# Payload.net
KiCad netlist of a schematic drawn in Altium Designer
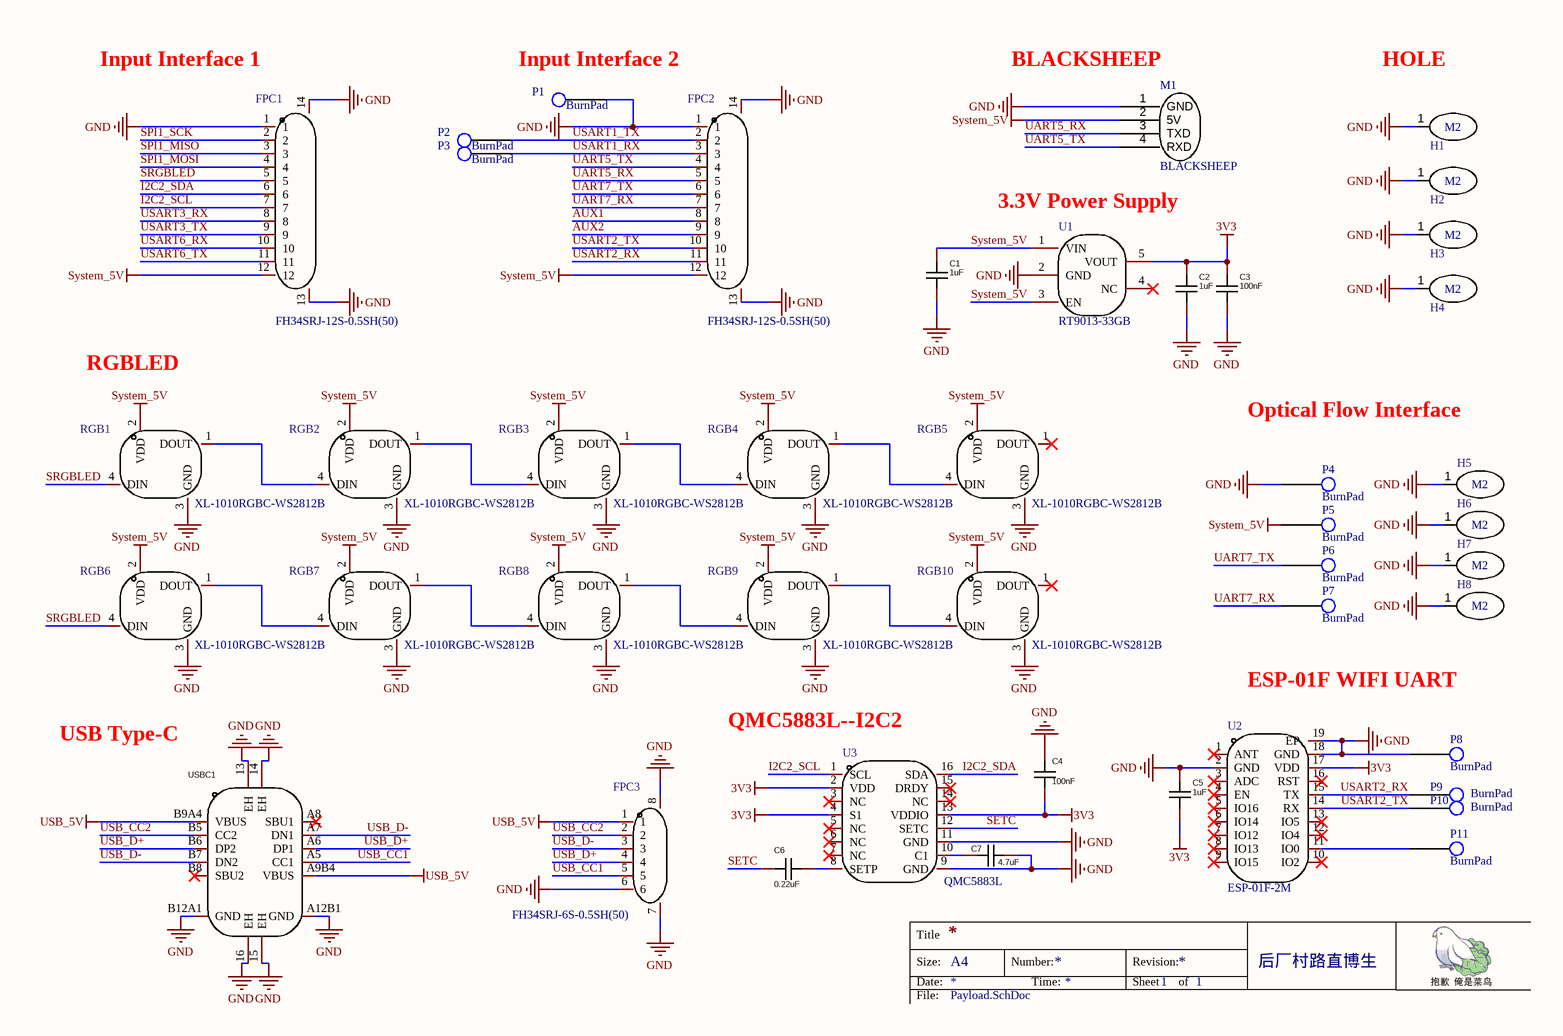
[diagram p0: Payload.SchDoc]

(export (version "E")
  (design (tool "Eeschema 10.0.6"))
  (components
    (comp (ref "C1")
      (value "1uF")
      (footprint "C0402")
      (libsource (lib "Capacitor") (part "CC0603KRX7R9BB104"))
    )
    (comp (ref "C2")
      (value "1uF")
      (footprint "C0402")
      (libsource (lib "Capacitor") (part "CC0603KRX7R9BB104"))
    )
    (comp (ref "C3")
      (value "100nF")
      (footprint "C0201")
      (libsource (lib "Capacitor") (part "CC0603KRX7R9BB104"))
    )
    (comp (ref "C4")
      (value "100nF")
      (footprint "C0201")
      (libsource (lib "Capacitor") (part "CC0603KRX7R9BB104"))
    )
    (comp (ref "C5")
      (value "1uF")
      (footprint "C0402")
      (libsource (lib "Capacitor") (part "CC0603KRX7R9BB104"))
    )
    (comp (ref "C6")
      (value "0.22uF")
      (footprint "C0402")
      (libsource (lib "Capacitor") (part "CC0603KRX7R9BB104"))
    )
    (comp (ref "C7")
      (value "4.7uF")
      (footprint "C0402")
      (libsource (lib "Capacitor") (part "CC0603KRX7R9BB104"))
    )
    (comp (ref "FPC1")
      (value "FH34SRJ-12S-0.5SH(50)")
      (footprint "FFC-SMD_12P-P0.50_FH34SRJ-12S-0.5SH")
      (fields (field (name "MANUFACTURER") "HRS(广濑)"))
      (libsource (lib "FPC") (part "FH34SRJ-12S-0.5SH(50)"))
    )
    (comp (ref "FPC2")
      (value "FH34SRJ-12S-0.5SH(50)")
      (footprint "FFC-SMD_12P-P0.50_FH34SRJ-12S-0.5SH")
      (fields (field (name "MANUFACTURER") "HRS(广濑)"))
      (libsource (lib "FPC") (part "FH34SRJ-12S-0.5SH(50)"))
    )
    (comp (ref "FPC3")
      (value "FH34SRJ-6S-0.5SH(50)")
      (footprint "FFC-SMD_6P-P0.50_FH34SRJ-6S-0.5SH")
      (fields (field (name "MANUFACTURER") "HRS(广濑)"))
      (libsource (lib "FPC") (part "FH34SRJ-6S-0.5SH(50)"))
    )
    (comp (ref "H1") (value "M2_HOLE") (footprint "M2_HOLE") (libsource (lib "HOLE") (part "M2_HOLE")))
    (comp (ref "H2") (value "M2_HOLE") (footprint "M2_HOLE") (libsource (lib "HOLE") (part "M2_HOLE")))
    (comp (ref "H3") (value "M2_HOLE") (footprint "M2_HOLE") (libsource (lib "HOLE") (part "M2_HOLE")))
    (comp (ref "H4") (value "M2_HOLE") (footprint "M2_HOLE") (libsource (lib "HOLE") (part "M2_HOLE")))
    (comp (ref "H5") (value "M2_HOLE") (footprint "M2_HOLE") (libsource (lib "HOLE") (part "M2_HOLE")))
    (comp (ref "H6") (value "M2_HOLE") (footprint "M2_HOLE") (libsource (lib "HOLE") (part "M2_HOLE")))
    (comp (ref "H7") (value "M2_HOLE") (footprint "M2_HOLE") (libsource (lib "HOLE") (part "M2_HOLE")))
    (comp (ref "H8") (value "M2_HOLE") (footprint "M2_HOLE") (libsource (lib "HOLE") (part "M2_HOLE")))
    (comp (ref "M1")
      (value "BLACKSHEEP")
      (footprint "BLACKSHEEP")
      (libsource (lib "Module") (part "BLACKSHEEP"))
    )
    (comp (ref "P1") (value "BurnPad") (footprint "BurnPad_0.8mm") (libsource (lib "Pad") (part "BurnPad")))
    (comp (ref "P2") (value "BurnPad") (footprint "BurnPad_0.8mm") (libsource (lib "Pad") (part "BurnPad")))
    (comp (ref "P3") (value "BurnPad") (footprint "BurnPad_0.8mm") (libsource (lib "Pad") (part "BurnPad")))
    (comp (ref "P4") (value "BurnPad") (footprint "BurnPad_0.8mm") (libsource (lib "Pad") (part "BurnPad")))
    (comp (ref "P5") (value "BurnPad") (footprint "BurnPad_0.8mm") (libsource (lib "Pad") (part "BurnPad")))
    (comp (ref "P6") (value "BurnPad") (footprint "BurnPad_0.8mm") (libsource (lib "Pad") (part "BurnPad")))
    (comp (ref "P7") (value "BurnPad") (footprint "BurnPad_0.8mm") (libsource (lib "Pad") (part "BurnPad")))
    (comp (ref "P8") (value "BurnPad") (footprint "BurnPad_0.8mm") (libsource (lib "Pad") (part "BurnPad")))
    (comp (ref "P9") (value "BurnPad") (footprint "BurnPad_0.8mm") (libsource (lib "Pad") (part "BurnPad")))
    (comp (ref "P10") (value "BurnPad") (footprint "BurnPad_0.8mm") (libsource (lib "Pad") (part "BurnPad")))
    (comp (ref "P11") (value "BurnPad") (footprint "BurnPad_0.8mm") (libsource (lib "Pad") (part "BurnPad")))
    (comp (ref "RGB1")
      (value "XL-1010RGBC-WS2812B")
      (footprint "LED-SMD_4P-L1.0-W1.0-TL_XL-1010RGBC-WS2812B")
      (fields (field (name "MANUFACTURER") "XINGLIGHT(成兴光)"))
      (libsource (lib "RGB") (part "XL-1010RGBC-WS2812B"))
    )
    (comp (ref "RGB2")
      (value "XL-1010RGBC-WS2812B")
      (footprint "LED-SMD_4P-L1.0-W1.0-TL_XL-1010RGBC-WS2812B")
      (fields (field (name "MANUFACTURER") "XINGLIGHT(成兴光)"))
      (libsource (lib "RGB") (part "XL-1010RGBC-WS2812B"))
    )
    (comp (ref "RGB3")
      (value "XL-1010RGBC-WS2812B")
      (footprint "LED-SMD_4P-L1.0-W1.0-TL_XL-1010RGBC-WS2812B")
      (fields (field (name "MANUFACTURER") "XINGLIGHT(成兴光)"))
      (libsource (lib "RGB") (part "XL-1010RGBC-WS2812B"))
    )
    (comp (ref "RGB4")
      (value "XL-1010RGBC-WS2812B")
      (footprint "LED-SMD_4P-L1.0-W1.0-TL_XL-1010RGBC-WS2812B")
      (fields (field (name "MANUFACTURER") "XINGLIGHT(成兴光)"))
      (libsource (lib "RGB") (part "XL-1010RGBC-WS2812B"))
    )
    (comp (ref "RGB5")
      (value "XL-1010RGBC-WS2812B")
      (footprint "LED-SMD_4P-L1.0-W1.0-TL_XL-1010RGBC-WS2812B")
      (fields (field (name "MANUFACTURER") "XINGLIGHT(成兴光)"))
      (libsource (lib "RGB") (part "XL-1010RGBC-WS2812B"))
    )
    (comp (ref "RGB6")
      (value "XL-1010RGBC-WS2812B")
      (footprint "LED-SMD_4P-L1.0-W1.0-TL_XL-1010RGBC-WS2812B")
      (fields (field (name "MANUFACTURER") "XINGLIGHT(成兴光)"))
      (libsource (lib "RGB") (part "XL-1010RGBC-WS2812B"))
    )
    (comp (ref "RGB7")
      (value "XL-1010RGBC-WS2812B")
      (footprint "LED-SMD_4P-L1.0-W1.0-TL_XL-1010RGBC-WS2812B")
      (fields (field (name "MANUFACTURER") "XINGLIGHT(成兴光)"))
      (libsource (lib "RGB") (part "XL-1010RGBC-WS2812B"))
    )
    (comp (ref "RGB8")
      (value "XL-1010RGBC-WS2812B")
      (footprint "LED-SMD_4P-L1.0-W1.0-TL_XL-1010RGBC-WS2812B")
      (fields (field (name "MANUFACTURER") "XINGLIGHT(成兴光)"))
      (libsource (lib "RGB") (part "XL-1010RGBC-WS2812B"))
    )
    (comp (ref "RGB9")
      (value "XL-1010RGBC-WS2812B")
      (footprint "LED-SMD_4P-L1.0-W1.0-TL_XL-1010RGBC-WS2812B")
      (fields (field (name "MANUFACTURER") "XINGLIGHT(成兴光)"))
      (libsource (lib "RGB") (part "XL-1010RGBC-WS2812B"))
    )
    (comp (ref "RGB10")
      (value "XL-1010RGBC-WS2812B")
      (footprint "LED-SMD_4P-L1.0-W1.0-TL_XL-1010RGBC-WS2812B")
      (fields (field (name "MANUFACTURER") "XINGLIGHT(成兴光)"))
      (libsource (lib "RGB") (part "XL-1010RGBC-WS2812B"))
    )
    (comp (ref "U1")
      (value "RT9013-33GB")
      (footprint "SOT-23-5")
      (fields (field (name "MANUFACTURER") "RICHTEK(立锜)"))
      (libsource (lib "Power") (part "RT9013-33GB"))
    )
    (comp (ref "U2")
      (value "ESP-01F-2M")
      (footprint "WIFIM-SMD_ESP-01F-2M")
      (fields (field (name "MANUFACTURER") "Ai-Thinker(安信可)"))
      (libsource (lib "Module") (part "ESP-01F-2M"))
    )
    (comp (ref "U3")
      (value "QMC5883L")
      (footprint "LGA-16_L3.0-W3.0-P0.50-BL_SQ")
      (fields (field (name "MANUFACTURER") "QST(上海矽睿)"))
      (libsource (lib "IMU") (part "QMC5883L"))
    )
    (comp (ref "USBC1")
      (value "918-418K2024S40000")
      (footprint "USB-C-SMD_TYPE-C-USB-4")
      (fields (field (name "MANUFACTURER") "精拓金"))
      (libsource (lib "TYPE-C") (part "918-418K2024S40000"))
    )
  )
  (nets
    (net (code "1") (name "/AUX1") (class "Default")
      (node (ref "FPC2") (pin "8") (pinfunction "8_8") (pintype "passive"))
    )
    (net (code "2") (name "/AUX2") (class "Default")
      (node (ref "FPC2") (pin "9") (pinfunction "9_9") (pintype "passive"))
    )
    (net (code "3") (name "/I2C2_SCL") (class "Default")
      (node (ref "FPC1") (pin "7") (pinfunction "7_7") (pintype "passive"))
      (node (ref "U3") (pin "1") (pinfunction "SCL_1") (pintype "passive"))
    )
    (net (code "4") (name "/I2C2_SDA") (class "Default")
      (node (ref "FPC1") (pin "6") (pinfunction "6_6") (pintype "passive"))
      (node (ref "U3") (pin "16") (pinfunction "SDA_16") (pintype "passive"))
    )
    (net (code "5") (name "/SETC") (class "Default")
      (node (ref "C6") (pin "2") (pinfunction "2_2") (pintype "passive"))
      (node (ref "U3") (pin "12") (pinfunction "SETC_12") (pintype "passive"))
    )
    (net (code "6") (name "/SPI1_MISO") (class "Default")
      (node (ref "FPC1") (pin "3") (pinfunction "3_3") (pintype "passive"))
    )
    (net (code "7") (name "/SPI1_MOSI") (class "Default")
      (node (ref "FPC1") (pin "4") (pinfunction "4_4") (pintype "passive"))
    )
    (net (code "8") (name "/SPI1_SCK") (class "Default")
      (node (ref "FPC1") (pin "2") (pinfunction "2_2") (pintype "passive"))
    )
    (net (code "9") (name "/SRGBLED") (class "Default")
      (node (ref "FPC1") (pin "5") (pinfunction "5_5") (pintype "passive"))
      (node (ref "RGB1") (pin "4") (pinfunction "DIN_4") (pintype "passive"))
      (node (ref "RGB6") (pin "4") (pinfunction "DIN_4") (pintype "passive"))
    )
    (net (code "10") (name "/UART5_RX") (class "Default")
      (node (ref "FPC2") (pin "5") (pinfunction "5_5") (pintype "passive"))
      (node (ref "M1") (pin "3") (pinfunction "TXD_3") (pintype "passive"))
    )
    (net (code "11") (name "/UART5_TX") (class "Default")
      (node (ref "FPC2") (pin "4") (pinfunction "4_4") (pintype "passive"))
      (node (ref "M1") (pin "4") (pinfunction "RXD_4") (pintype "passive"))
    )
    (net (code "12") (name "/UART7_RX") (class "Default")
      (node (ref "FPC2") (pin "7") (pinfunction "7_7") (pintype "passive"))
      (node (ref "P7") (pin "1") (pinfunction "1_1") (pintype "passive"))
    )
    (net (code "13") (name "/UART7_TX") (class "Default")
      (node (ref "FPC2") (pin "6") (pinfunction "6_6") (pintype "passive"))
      (node (ref "P6") (pin "1") (pinfunction "1_1") (pintype "passive"))
    )
    (net (code "14") (name "/USART1_RX") (class "Default")
      (node (ref "FPC2") (pin "3") (pinfunction "3_3") (pintype "passive"))
      (node (ref "P3") (pin "1") (pinfunction "1_1") (pintype "passive"))
    )
    (net (code "15") (name "/USART1_TX") (class "Default")
      (node (ref "FPC2") (pin "2") (pinfunction "2_2") (pintype "passive"))
      (node (ref "P2") (pin "1") (pinfunction "1_1") (pintype "passive"))
    )
    (net (code "16") (name "/USART2_RX") (class "Default")
      (node (ref "FPC2") (pin "11") (pinfunction "11_11") (pintype "passive"))
      (node (ref "P9") (pin "1") (pinfunction "1_1") (pintype "passive"))
      (node (ref "U2") (pin "15") (pinfunction "TX_15") (pintype "passive"))
    )
    (net (code "17") (name "/USART2_TX") (class "Default")
      (node (ref "FPC2") (pin "10") (pinfunction "10_10") (pintype "passive"))
      (node (ref "P10") (pin "1") (pinfunction "1_1") (pintype "passive"))
      (node (ref "U2") (pin "14") (pinfunction "RX_14") (pintype "passive"))
    )
    (net (code "18") (name "/USART3_RX") (class "Default")
      (node (ref "FPC1") (pin "8") (pinfunction "8_8") (pintype "passive"))
    )
    (net (code "19") (name "/USART3_TX") (class "Default")
      (node (ref "FPC1") (pin "9") (pinfunction "9_9") (pintype "passive"))
    )
    (net (code "20") (name "/USART6_RX") (class "Default")
      (node (ref "FPC1") (pin "10") (pinfunction "10_10") (pintype "passive"))
    )
    (net (code "21") (name "/USART6_TX") (class "Default")
      (node (ref "FPC1") (pin "11") (pinfunction "11_11") (pintype "passive"))
    )
    (net (code "22") (name "/USB_CC1") (class "Default")
      (node (ref "FPC3") (pin "5") (pinfunction "5_5") (pintype "passive"))
      (node (ref "USBC1") (pin "A5") (pinfunction "CC1_A5") (pintype "passive"))
    )
    (net (code "23") (name "/USB_CC2") (class "Default")
      (node (ref "FPC3") (pin "2") (pinfunction "2_2") (pintype "passive"))
      (node (ref "USBC1") (pin "B5") (pinfunction "CC2_B5") (pintype "passive"))
    )
    (net (code "24") (name "/USB_D+") (class "Default")
      (node (ref "FPC3") (pin "4") (pinfunction "4_4") (pintype "passive"))
      (node (ref "USBC1") (pin "A6") (pinfunction "DP1_A6") (pintype "passive"))
      (node (ref "USBC1") (pin "B6") (pinfunction "DP2_B6") (pintype "passive"))
    )
    (net (code "25") (name "/USB_D-") (class "Default")
      (node (ref "FPC3") (pin "3") (pinfunction "3_3") (pintype "passive"))
      (node (ref "USBC1") (pin "A7") (pinfunction "DN1_A7") (pintype "passive"))
      (node (ref "USBC1") (pin "B7") (pinfunction "DN2_B7") (pintype "passive"))
    )
    (net (code "26") (name "3V3") (class "Default")
      (node (ref "C2") (pin "1") (pinfunction "1_1") (pintype "passive"))
      (node (ref "C3") (pin "1") (pinfunction "1_1") (pintype "passive"))
      (node (ref "C4") (pin "1") (pinfunction "1_1") (pintype "passive"))
      (node (ref "C5") (pin "2") (pinfunction "2_2") (pintype "passive"))
      (node (ref "U1") (pin "5") (pinfunction "VOUT_5") (pintype "passive"))
      (node (ref "U2") (pin "17") (pinfunction "VDD_17") (pintype "passive"))
      (node (ref "U3") (pin "13") (pinfunction "VDDIO_13") (pintype "passive"))
      (node (ref "U3") (pin "2") (pinfunction "VDD_2") (pintype "passive"))
      (node (ref "U3") (pin "4") (pinfunction "S1_4") (pintype "passive"))
    )
    (net (code "27") (name "GND") (class "Default")
      (node (ref "C1") (pin "2") (pinfunction "2_2") (pintype "passive"))
      (node (ref "C2") (pin "2") (pinfunction "2_2") (pintype "passive"))
      (node (ref "C3") (pin "2") (pinfunction "2_2") (pintype "passive"))
      (node (ref "C4") (pin "2") (pinfunction "2_2") (pintype "passive"))
      (node (ref "C5") (pin "1") (pinfunction "1_1") (pintype "passive"))
      (node (ref "C7") (pin "1") (pinfunction "1_1") (pintype "passive"))
      (node (ref "FPC1") (pin "1") (pinfunction "1_1") (pintype "passive"))
      (node (ref "FPC1") (pin "13") (pinfunction "13_13") (pintype "passive"))
      (node (ref "FPC1") (pin "14") (pinfunction "14_14") (pintype "passive"))
      (node (ref "FPC2") (pin "1") (pinfunction "1_1") (pintype "passive"))
      (node (ref "FPC2") (pin "13") (pinfunction "13_13") (pintype "passive"))
      (node (ref "FPC2") (pin "14") (pinfunction "14_14") (pintype "passive"))
      (node (ref "FPC3") (pin "6") (pinfunction "6_6") (pintype "passive"))
      (node (ref "FPC3") (pin "7") (pinfunction "7_7") (pintype "passive"))
      (node (ref "FPC3") (pin "8") (pinfunction "8_8") (pintype "passive"))
      (node (ref "H1") (pin "1") (pinfunction "1_1") (pintype "passive"))
      (node (ref "H2") (pin "1") (pinfunction "1_1") (pintype "passive"))
      (node (ref "H3") (pin "1") (pinfunction "1_1") (pintype "passive"))
      (node (ref "H4") (pin "1") (pinfunction "1_1") (pintype "passive"))
      (node (ref "H5") (pin "1") (pinfunction "1_1") (pintype "passive"))
      (node (ref "H6") (pin "1") (pinfunction "1_1") (pintype "passive"))
      (node (ref "H7") (pin "1") (pinfunction "1_1") (pintype "passive"))
      (node (ref "H8") (pin "1") (pinfunction "1_1") (pintype "passive"))
      (node (ref "M1") (pin "1") (pinfunction "GND_1") (pintype "passive"))
      (node (ref "P1") (pin "1") (pinfunction "1_1") (pintype "passive"))
      (node (ref "P4") (pin "1") (pinfunction "1_1") (pintype "passive"))
      (node (ref "P8") (pin "1") (pinfunction "1_1") (pintype "passive"))
      (node (ref "RGB1") (pin "3") (pinfunction "GND_3") (pintype "passive"))
      (node (ref "RGB10") (pin "3") (pinfunction "GND_3") (pintype "passive"))
      (node (ref "RGB2") (pin "3") (pinfunction "GND_3") (pintype "passive"))
      (node (ref "RGB3") (pin "3") (pinfunction "GND_3") (pintype "passive"))
      (node (ref "RGB4") (pin "3") (pinfunction "GND_3") (pintype "passive"))
      (node (ref "RGB5") (pin "3") (pinfunction "GND_3") (pintype "passive"))
      (node (ref "RGB6") (pin "3") (pinfunction "GND_3") (pintype "passive"))
      (node (ref "RGB7") (pin "3") (pinfunction "GND_3") (pintype "passive"))
      (node (ref "RGB8") (pin "3") (pinfunction "GND_3") (pintype "passive"))
      (node (ref "RGB9") (pin "3") (pinfunction "GND_3") (pintype "passive"))
      (node (ref "U1") (pin "2") (pinfunction "GND_2") (pintype "passive"))
      (node (ref "U2") (pin "18") (pinfunction "GND_18") (pintype "passive"))
      (node (ref "U2") (pin "19") (pinfunction "EP_19") (pintype "passive"))
      (node (ref "U2") (pin "2") (pinfunction "GND_2") (pintype "passive"))
      (node (ref "U3") (pin "11") (pinfunction "GND_11") (pintype "passive"))
      (node (ref "U3") (pin "9") (pinfunction "GND_9") (pintype "passive"))
      (node (ref "USBC1") (pin "13") (pinfunction "EH_13") (pintype "passive"))
      (node (ref "USBC1") (pin "14") (pinfunction "EH_14") (pintype "passive"))
      (node (ref "USBC1") (pin "15") (pinfunction "EH_15") (pintype "passive"))
      (node (ref "USBC1") (pin "16") (pinfunction "EH_16") (pintype "passive"))
      (node (ref "USBC1") (pin "A12B1") (pinfunction "GND_A12B1") (pintype "passive"))
      (node (ref "USBC1") (pin "B12A1") (pinfunction "GND_B12A1") (pintype "passive"))
    )
    (net (code "28") (name "Net-(RGB1-DOUT)") (class "Default")
      (node (ref "RGB1") (pin "1") (pinfunction "DOUT_1") (pintype "passive"))
      (node (ref "RGB2") (pin "4") (pinfunction "DIN_4") (pintype "passive"))
    )
    (net (code "29") (name "Net-(RGB2-DOUT)") (class "Default")
      (node (ref "RGB2") (pin "1") (pinfunction "DOUT_1") (pintype "passive"))
      (node (ref "RGB3") (pin "4") (pinfunction "DIN_4") (pintype "passive"))
    )
    (net (code "30") (name "Net-(RGB3-DOUT)") (class "Default")
      (node (ref "RGB3") (pin "1") (pinfunction "DOUT_1") (pintype "passive"))
      (node (ref "RGB4") (pin "4") (pinfunction "DIN_4") (pintype "passive"))
    )
    (net (code "31") (name "Net-(RGB4-DOUT)") (class "Default")
      (node (ref "RGB4") (pin "1") (pinfunction "DOUT_1") (pintype "passive"))
      (node (ref "RGB5") (pin "4") (pinfunction "DIN_4") (pintype "passive"))
    )
    (net (code "32") (name "Net-(RGB6-DOUT)") (class "Default")
      (node (ref "RGB6") (pin "1") (pinfunction "DOUT_1") (pintype "passive"))
      (node (ref "RGB7") (pin "4") (pinfunction "DIN_4") (pintype "passive"))
    )
    (net (code "33") (name "Net-(RGB7-DOUT)") (class "Default")
      (node (ref "RGB7") (pin "1") (pinfunction "DOUT_1") (pintype "passive"))
      (node (ref "RGB8") (pin "4") (pinfunction "DIN_4") (pintype "passive"))
    )
    (net (code "34") (name "Net-(RGB8-DOUT)") (class "Default")
      (node (ref "RGB8") (pin "1") (pinfunction "DOUT_1") (pintype "passive"))
      (node (ref "RGB9") (pin "4") (pinfunction "DIN_4") (pintype "passive"))
    )
    (net (code "35") (name "Net-(RGB10-DIN)") (class "Default")
      (node (ref "RGB10") (pin "4") (pinfunction "DIN_4") (pintype "passive"))
      (node (ref "RGB9") (pin "1") (pinfunction "DOUT_1") (pintype "passive"))
    )
    (net (code "36") (name "Net-(U2-IO0)") (class "Default")
      (node (ref "P11") (pin "1") (pinfunction "1_1") (pintype "passive"))
      (node (ref "U2") (pin "11") (pinfunction "IO0_11") (pintype "passive"))
    )
    (net (code "37") (name "Net-(U3-C1)") (class "Default")
      (node (ref "C7") (pin "2") (pinfunction "2_2") (pintype "passive"))
      (node (ref "U3") (pin "10") (pinfunction "C1_10") (pintype "passive"))
    )
    (net (code "38") (name "Net-(U3-SETP)") (class "Default")
      (node (ref "C6") (pin "1") (pinfunction "1_1") (pintype "passive"))
      (node (ref "U3") (pin "8") (pinfunction "SETP_8") (pintype "passive"))
    )
    (net (code "39") (name "System_5V") (class "Default")
      (node (ref "C1") (pin "1") (pinfunction "1_1") (pintype "passive"))
      (node (ref "FPC1") (pin "12") (pinfunction "12_12") (pintype "passive"))
      (node (ref "FPC2") (pin "12") (pinfunction "12_12") (pintype "passive"))
      (node (ref "M1") (pin "2") (pinfunction "5V_2") (pintype "passive"))
      (node (ref "P5") (pin "1") (pinfunction "1_1") (pintype "passive"))
      (node (ref "RGB1") (pin "2") (pinfunction "VDD_2") (pintype "passive"))
      (node (ref "RGB10") (pin "2") (pinfunction "VDD_2") (pintype "passive"))
      (node (ref "RGB2") (pin "2") (pinfunction "VDD_2") (pintype "passive"))
      (node (ref "RGB3") (pin "2") (pinfunction "VDD_2") (pintype "passive"))
      (node (ref "RGB4") (pin "2") (pinfunction "VDD_2") (pintype "passive"))
      (node (ref "RGB5") (pin "2") (pinfunction "VDD_2") (pintype "passive"))
      (node (ref "RGB6") (pin "2") (pinfunction "VDD_2") (pintype "passive"))
      (node (ref "RGB7") (pin "2") (pinfunction "VDD_2") (pintype "passive"))
      (node (ref "RGB8") (pin "2") (pinfunction "VDD_2") (pintype "passive"))
      (node (ref "RGB9") (pin "2") (pinfunction "VDD_2") (pintype "passive"))
      (node (ref "U1") (pin "1") (pinfunction "VIN_1") (pintype "passive"))
      (node (ref "U1") (pin "3") (pinfunction "EN_3") (pintype "passive"))
    )
    (net (code "40") (name "USB_5V") (class "Default")
      (node (ref "FPC3") (pin "1") (pinfunction "1_1") (pintype "passive"))
      (node (ref "USBC1") (pin "A9B4") (pinfunction "VBUS_A9B4") (pintype "passive"))
      (node (ref "USBC1") (pin "B9A4") (pinfunction "VBUS_B9A4") (pintype "passive"))
    )
    (net (code "41") (name "unconnected-(RGB5-DOUT-Pad1)") (class "Default")
      (node (ref "RGB5") (pin "1") (pinfunction "DOUT_1") (pintype "passive+no_connect"))
    )
    (net (code "42") (name "unconnected-(RGB10-DOUT-Pad1)") (class "Default")
      (node (ref "RGB10") (pin "1") (pinfunction "DOUT_1") (pintype "passive+no_connect"))
    )
    (net (code "43") (name "unconnected-(U1-NC-Pad4)") (class "Default")
      (node (ref "U1") (pin "4") (pinfunction "NC_4") (pintype "passive+no_connect"))
    )
    (net (code "44") (name "unconnected-(U2-ADC-Pad3)") (class "Default")
      (node (ref "U2") (pin "3") (pinfunction "ADC_3") (pintype "passive+no_connect"))
    )
    (net (code "45") (name "unconnected-(U2-ANT-Pad1)") (class "Default")
      (node (ref "U2") (pin "1") (pinfunction "ANT_1") (pintype "passive+no_connect"))
    )
    (net (code "46") (name "unconnected-(U2-EN-Pad4)") (class "Default")
      (node (ref "U2") (pin "4") (pinfunction "EN_4") (pintype "passive+no_connect"))
    )
    (net (code "47") (name "unconnected-(U2-IO2-Pad10)") (class "Default")
      (node (ref "U2") (pin "10") (pinfunction "IO2_10") (pintype "passive+no_connect"))
    )
    (net (code "48") (name "unconnected-(U2-IO4-Pad12)") (class "Default")
      (node (ref "U2") (pin "12") (pinfunction "IO4_12") (pintype "passive+no_connect"))
    )
    (net (code "49") (name "unconnected-(U2-IO5-Pad13)") (class "Default")
      (node (ref "U2") (pin "13") (pinfunction "IO5_13") (pintype "passive+no_connect"))
    )
    (net (code "50") (name "unconnected-(U2-IO12-Pad7)") (class "Default")
      (node (ref "U2") (pin "7") (pinfunction "IO12_7") (pintype "passive+no_connect"))
    )
    (net (code "51") (name "unconnected-(U2-IO13-Pad8)") (class "Default")
      (node (ref "U2") (pin "8") (pinfunction "IO13_8") (pintype "passive+no_connect"))
    )
    (net (code "52") (name "unconnected-(U2-IO14-Pad6)") (class "Default")
      (node (ref "U2") (pin "6") (pinfunction "IO14_6") (pintype "passive+no_connect"))
    )
    (net (code "53") (name "unconnected-(U2-IO15-Pad9)") (class "Default")
      (node (ref "U2") (pin "9") (pinfunction "IO15_9") (pintype "passive+no_connect"))
    )
    (net (code "54") (name "unconnected-(U2-IO16-Pad5)") (class "Default")
      (node (ref "U2") (pin "5") (pinfunction "IO16_5") (pintype "passive+no_connect"))
    )
    (net (code "55") (name "unconnected-(U2-RST-Pad16)") (class "Default")
      (node (ref "U2") (pin "16") (pinfunction "RST_16") (pintype "passive+no_connect"))
    )
    (net (code "56") (name "unconnected-(U3-DRDY-Pad15)") (class "Default")
      (node (ref "U3") (pin "15") (pinfunction "DRDY_15") (pintype "passive+no_connect"))
    )
    (net (code "57") (name "unconnected-(U3-NC-Pad3)") (class "Default")
      (node (ref "U3") (pin "3") (pinfunction "NC_3") (pintype "passive+no_connect"))
    )
    (net (code "58") (name "unconnected-(U3-NC-Pad5)") (class "Default")
      (node (ref "U3") (pin "5") (pinfunction "NC_5") (pintype "passive+no_connect"))
    )
    (net (code "59") (name "unconnected-(U3-NC-Pad6)") (class "Default")
      (node (ref "U3") (pin "6") (pinfunction "NC_6") (pintype "passive+no_connect"))
    )
    (net (code "60") (name "unconnected-(U3-NC-Pad7)") (class "Default")
      (node (ref "U3") (pin "7") (pinfunction "NC_7") (pintype "passive+no_connect"))
    )
    (net (code "61") (name "unconnected-(U3-NC-Pad14)") (class "Default")
      (node (ref "U3") (pin "14") (pinfunction "NC_14") (pintype "passive+no_connect"))
    )
    (net (code "62") (name "unconnected-(USBC1-SBU1-PadA8)") (class "Default")
      (node (ref "USBC1") (pin "A8") (pinfunction "SBU1_A8") (pintype "passive+no_connect"))
    )
    (net (code "63") (name "unconnected-(USBC1-SBU2-PadB8)") (class "Default")
      (node (ref "USBC1") (pin "B8") (pinfunction "SBU2_B8") (pintype "passive+no_connect"))
    )
  )
)
